# e-Tapperhandpiece11.net
KiCad netlist of a schematic drawn in EAGLE
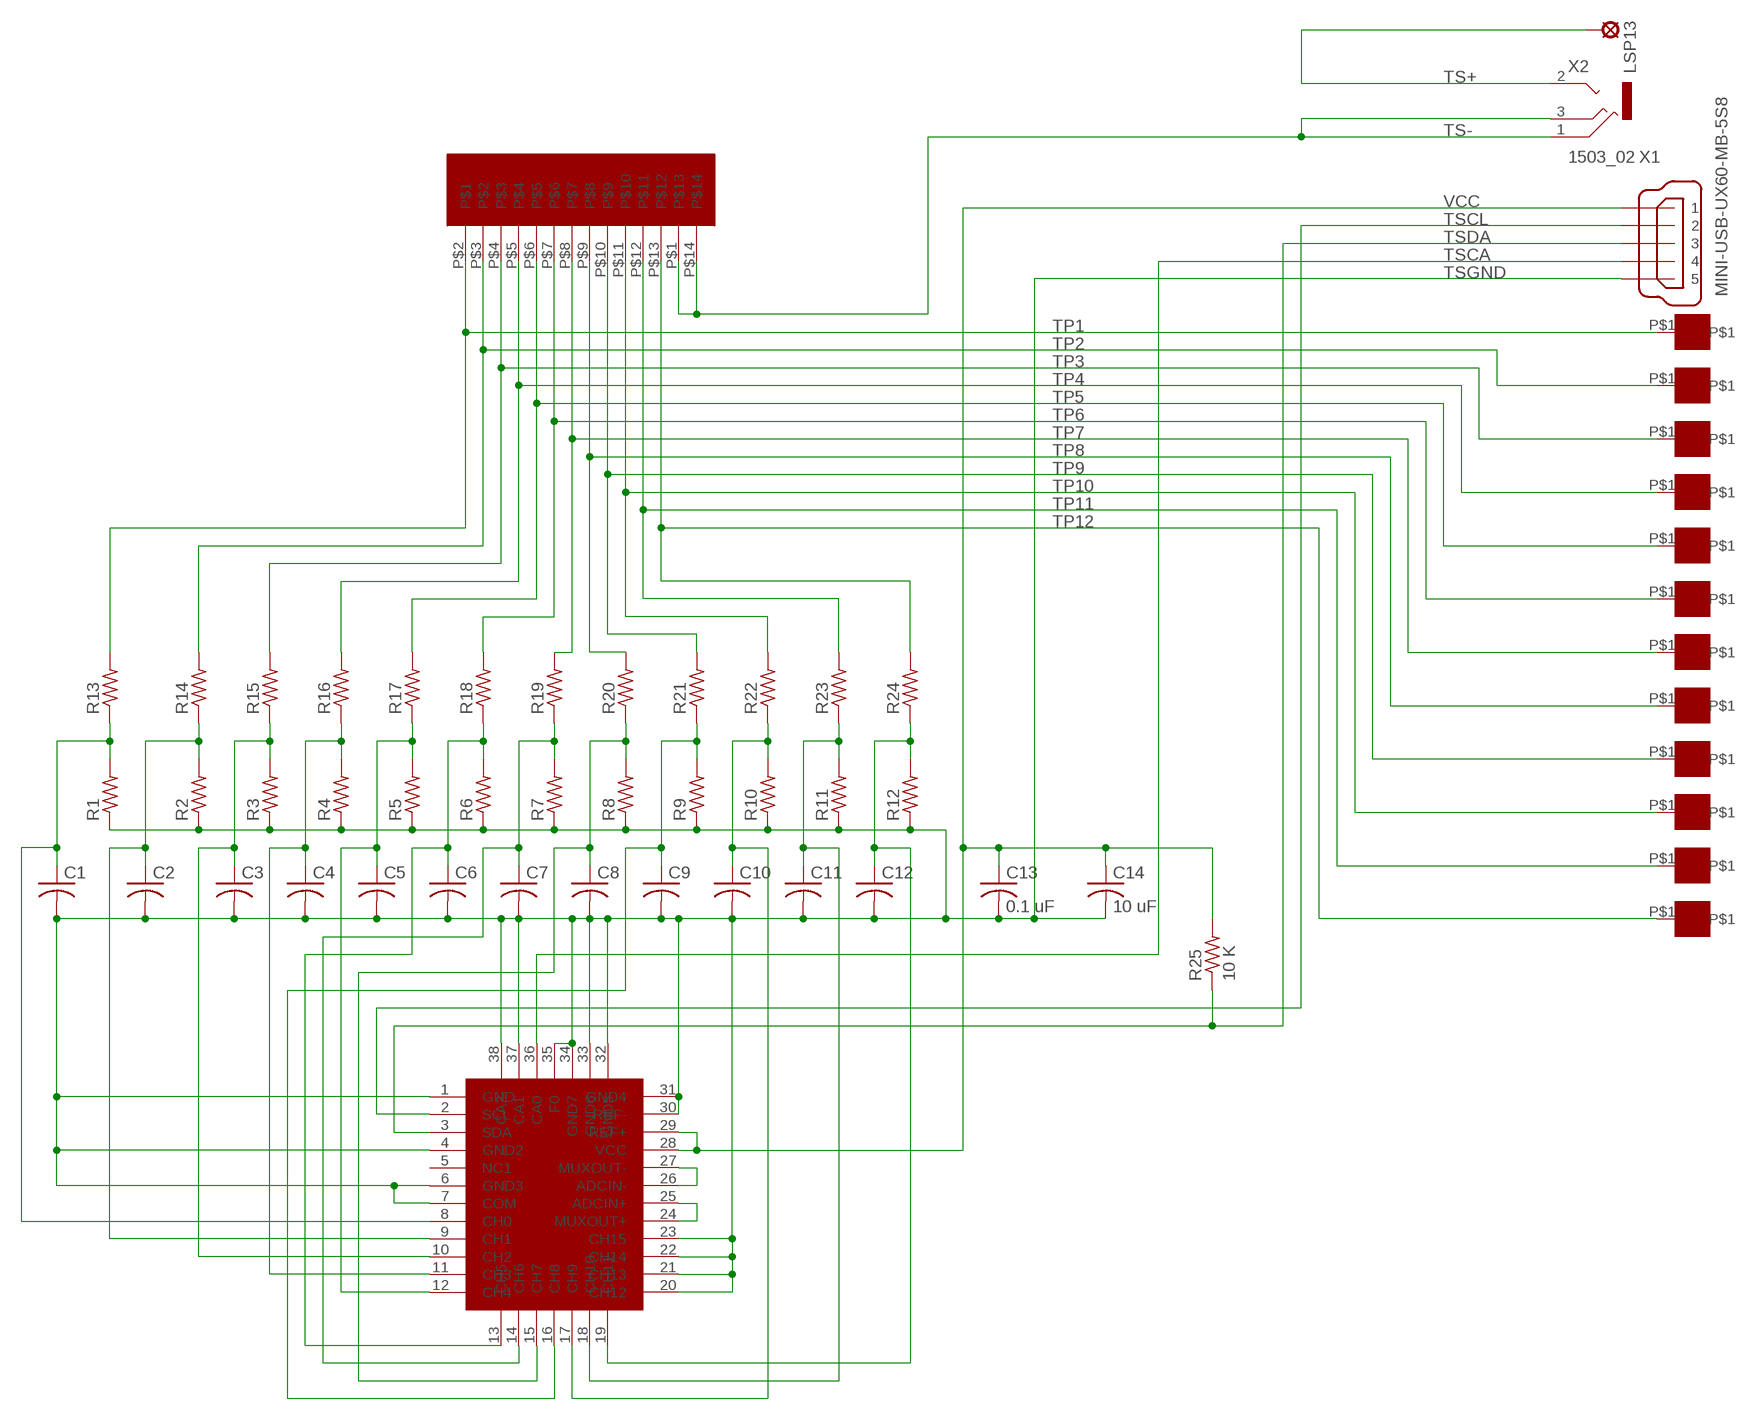
[diagram p0: schematic, sheet 1]

(export (version "E")
  (design (tool "Eeschema 10.0.6"))
  (components
    (comp (ref "C1")
      (value "C-USC0603")
      (footprint "eagle-import:C0603")
      (libsource (lib "eagle-import") (part "C-USC0603"))
    )
    (comp (ref "C2")
      (value "C-USC0603")
      (footprint "eagle-import:C0603")
      (libsource (lib "eagle-import") (part "C-USC0603"))
    )
    (comp (ref "C3")
      (value "C-USC0603")
      (footprint "eagle-import:C0603")
      (libsource (lib "eagle-import") (part "C-USC0603"))
    )
    (comp (ref "C4")
      (value "C-USC0603")
      (footprint "eagle-import:C0603")
      (libsource (lib "eagle-import") (part "C-USC0603"))
    )
    (comp (ref "C5")
      (value "C-USC0603")
      (footprint "eagle-import:C0603")
      (libsource (lib "eagle-import") (part "C-USC0603"))
    )
    (comp (ref "C6")
      (value "C-USC0603")
      (footprint "eagle-import:C0603")
      (libsource (lib "eagle-import") (part "C-USC0603"))
    )
    (comp (ref "C7")
      (value "C-USC0603")
      (footprint "eagle-import:C0603")
      (libsource (lib "eagle-import") (part "C-USC0603"))
    )
    (comp (ref "C8")
      (value "C-USC0603")
      (footprint "eagle-import:C0603")
      (libsource (lib "eagle-import") (part "C-USC0603"))
    )
    (comp (ref "C9")
      (value "C-USC0603")
      (footprint "eagle-import:C0603")
      (libsource (lib "eagle-import") (part "C-USC0603"))
    )
    (comp (ref "C10")
      (value "C-USC0603")
      (footprint "eagle-import:C0603")
      (libsource (lib "eagle-import") (part "C-USC0603"))
    )
    (comp (ref "C11")
      (value "C-USC0603")
      (footprint "eagle-import:C0603")
      (libsource (lib "eagle-import") (part "C-USC0603"))
    )
    (comp (ref "C12")
      (value "C-USC0603")
      (footprint "eagle-import:C0603")
      (libsource (lib "eagle-import") (part "C-USC0603"))
    )
    (comp (ref "C13")
      (value "0.1 uF")
      (footprint "eagle-import:C0603")
      (libsource (lib "eagle-import") (part "C-USC0603"))
    )
    (comp (ref "C14")
      (value "10 uF")
      (footprint "eagle-import:C0805")
      (libsource (lib "eagle-import") (part "C-USC0805"))
    )
    (comp (ref "LSP13")
      (value "SE11")
      (footprint "eagle-import:SE11")
      (libsource (lib "eagle-import") (part "SE11"))
    )
    (comp (ref "R1")
      (value "R-US_R0402")
      (footprint "eagle-import:R0402")
      (libsource (lib "eagle-import") (part "R-US_R0402"))
    )
    (comp (ref "R2")
      (value "R-US_R0402")
      (footprint "eagle-import:R0402")
      (libsource (lib "eagle-import") (part "R-US_R0402"))
    )
    (comp (ref "R3")
      (value "R-US_R0402")
      (footprint "eagle-import:R0402")
      (libsource (lib "eagle-import") (part "R-US_R0402"))
    )
    (comp (ref "R4")
      (value "R-US_R0402")
      (footprint "eagle-import:R0402")
      (libsource (lib "eagle-import") (part "R-US_R0402"))
    )
    (comp (ref "R5")
      (value "R-US_R0402")
      (footprint "eagle-import:R0402")
      (libsource (lib "eagle-import") (part "R-US_R0402"))
    )
    (comp (ref "R6")
      (value "R-US_R0402")
      (footprint "eagle-import:R0402")
      (libsource (lib "eagle-import") (part "R-US_R0402"))
    )
    (comp (ref "R7")
      (value "R-US_R0402")
      (footprint "eagle-import:R0402")
      (libsource (lib "eagle-import") (part "R-US_R0402"))
    )
    (comp (ref "R8")
      (value "R-US_R0402")
      (footprint "eagle-import:R0402")
      (libsource (lib "eagle-import") (part "R-US_R0402"))
    )
    (comp (ref "R9")
      (value "R-US_R0402")
      (footprint "eagle-import:R0402")
      (libsource (lib "eagle-import") (part "R-US_R0402"))
    )
    (comp (ref "R10")
      (value "R-US_R0402")
      (footprint "eagle-import:R0402")
      (libsource (lib "eagle-import") (part "R-US_R0402"))
    )
    (comp (ref "R11")
      (value "R-US_R0402")
      (footprint "eagle-import:R0402")
      (libsource (lib "eagle-import") (part "R-US_R0402"))
    )
    (comp (ref "R12")
      (value "R-US_R0402")
      (footprint "eagle-import:R0402")
      (libsource (lib "eagle-import") (part "R-US_R0402"))
    )
    (comp (ref "R13")
      (value "R-US_R0402")
      (footprint "eagle-import:R0402")
      (libsource (lib "eagle-import") (part "R-US_R0402"))
    )
    (comp (ref "R14")
      (value "R-US_R0402")
      (footprint "eagle-import:R0402")
      (libsource (lib "eagle-import") (part "R-US_R0402"))
    )
    (comp (ref "R15")
      (value "R-US_R0402")
      (footprint "eagle-import:R0402")
      (libsource (lib "eagle-import") (part "R-US_R0402"))
    )
    (comp (ref "R16")
      (value "R-US_R0402")
      (footprint "eagle-import:R0402")
      (libsource (lib "eagle-import") (part "R-US_R0402"))
    )
    (comp (ref "R17")
      (value "R-US_R0402")
      (footprint "eagle-import:R0402")
      (libsource (lib "eagle-import") (part "R-US_R0402"))
    )
    (comp (ref "R18")
      (value "R-US_R0402")
      (footprint "eagle-import:R0402")
      (libsource (lib "eagle-import") (part "R-US_R0402"))
    )
    (comp (ref "R19")
      (value "R-US_R0402")
      (footprint "eagle-import:R0402")
      (libsource (lib "eagle-import") (part "R-US_R0402"))
    )
    (comp (ref "R20")
      (value "R-US_R0402")
      (footprint "eagle-import:R0402")
      (libsource (lib "eagle-import") (part "R-US_R0402"))
    )
    (comp (ref "R21")
      (value "R-US_R0402")
      (footprint "eagle-import:R0402")
      (libsource (lib "eagle-import") (part "R-US_R0402"))
    )
    (comp (ref "R22")
      (value "R-US_R0402")
      (footprint "eagle-import:R0402")
      (libsource (lib "eagle-import") (part "R-US_R0402"))
    )
    (comp (ref "R23")
      (value "R-US_R0402")
      (footprint "eagle-import:R0402")
      (libsource (lib "eagle-import") (part "R-US_R0402"))
    )
    (comp (ref "R24")
      (value "R-US_R0402")
      (footprint "eagle-import:R0402")
      (libsource (lib "eagle-import") (part "R-US_R0402"))
    )
    (comp (ref "R25")
      (value "10 K")
      (footprint "eagle-import:R0402")
      (libsource (lib "eagle-import") (part "R-US_R0402"))
    )
    (comp (ref "TSP1")
      (value "ET1")
      (footprint "eagle-import:ET1")
      (libsource (lib "eagle-import") (part "ET1"))
    )
    (comp (ref "TSP2")
      (value "ET1")
      (footprint "eagle-import:ET1")
      (libsource (lib "eagle-import") (part "ET1"))
    )
    (comp (ref "TSP3")
      (value "ET1")
      (footprint "eagle-import:ET1")
      (libsource (lib "eagle-import") (part "ET1"))
    )
    (comp (ref "TSP4")
      (value "ET1")
      (footprint "eagle-import:ET1")
      (libsource (lib "eagle-import") (part "ET1"))
    )
    (comp (ref "TSP5")
      (value "ET1")
      (footprint "eagle-import:ET1")
      (libsource (lib "eagle-import") (part "ET1"))
    )
    (comp (ref "TSP6")
      (value "ET1")
      (footprint "eagle-import:ET1")
      (libsource (lib "eagle-import") (part "ET1"))
    )
    (comp (ref "TSP7")
      (value "ET1")
      (footprint "eagle-import:ET1")
      (libsource (lib "eagle-import") (part "ET1"))
    )
    (comp (ref "TSP8")
      (value "ET1")
      (footprint "eagle-import:ET1")
      (libsource (lib "eagle-import") (part "ET1"))
    )
    (comp (ref "TSP9")
      (value "ET1")
      (footprint "eagle-import:ET1")
      (libsource (lib "eagle-import") (part "ET1"))
    )
    (comp (ref "TSP10")
      (value "ET1")
      (footprint "eagle-import:ET1")
      (libsource (lib "eagle-import") (part "ET1"))
    )
    (comp (ref "TSP11")
      (value "ET1")
      (footprint "eagle-import:ET1")
      (libsource (lib "eagle-import") (part "ET1"))
    )
    (comp (ref "TSP12")
      (value "ET1")
      (footprint "eagle-import:ET1")
      (libsource (lib "eagle-import") (part "ET1"))
    )
    (comp (ref "U$1")
      (value "LTC2497")
      (footprint "eagle-import:QFN38-5X7")
      (libsource (lib "eagle-import") (part "LTC2497"))
    )
    (comp (ref "U$2")
      (value "SS112D01")
      (footprint "eagle-import:SS112D01")
      (libsource (lib "eagle-import") (part "SS112D01"))
    )
    (comp (ref "X1")
      (value "MINI-USB-UX60-MB-5S8")
      (footprint "eagle-import:UX60-MB-5S8")
      (libsource (lib "eagle-import") (part "MINI-USB-UX60-MB-5S8"))
    )
    (comp (ref "X2")
      (value "1503_02")
      (footprint "eagle-import:1503_02")
      (libsource (lib "eagle-import") (part "1503_02"))
    )
  )
  (nets
    (net (code "1") (name "/TP1") (class "Default")
      (node (ref "R13") (pin "2") (pinfunction "2_2") (pintype "passive"))
      (node (ref "TSP1") (pin "P$1") (pinfunction "P$1_P$1") (pintype "bidirectional"))
      (node (ref "U$2") (pin "P$2") (pinfunction "P$1_P$2") (pintype "bidirectional"))
    )
    (net (code "2") (name "/TP2") (class "Default")
      (node (ref "R14") (pin "2") (pinfunction "2_2") (pintype "passive"))
      (node (ref "TSP2") (pin "P$1") (pinfunction "P$1_P$1") (pintype "bidirectional"))
      (node (ref "U$2") (pin "P$3") (pinfunction "P$2_P$3") (pintype "bidirectional"))
    )
    (net (code "3") (name "/TP3") (class "Default")
      (node (ref "R15") (pin "2") (pinfunction "2_2") (pintype "passive"))
      (node (ref "TSP3") (pin "P$1") (pinfunction "P$1_P$1") (pintype "bidirectional"))
      (node (ref "U$2") (pin "P$4") (pinfunction "P$3_P$4") (pintype "bidirectional"))
    )
    (net (code "4") (name "/TP4") (class "Default")
      (node (ref "R16") (pin "2") (pinfunction "2_2") (pintype "passive"))
      (node (ref "TSP4") (pin "P$1") (pinfunction "P$1_P$1") (pintype "bidirectional"))
      (node (ref "U$2") (pin "P$5") (pinfunction "P$4_P$5") (pintype "bidirectional"))
    )
    (net (code "5") (name "/TP5") (class "Default")
      (node (ref "R17") (pin "2") (pinfunction "2_2") (pintype "passive"))
      (node (ref "TSP5") (pin "P$1") (pinfunction "P$1_P$1") (pintype "bidirectional"))
      (node (ref "U$2") (pin "P$6") (pinfunction "P$5_P$6") (pintype "bidirectional"))
    )
    (net (code "6") (name "/TP6") (class "Default")
      (node (ref "R18") (pin "2") (pinfunction "2_2") (pintype "passive"))
      (node (ref "TSP6") (pin "P$1") (pinfunction "P$1_P$1") (pintype "bidirectional"))
      (node (ref "U$2") (pin "P$7") (pinfunction "P$6_P$7") (pintype "bidirectional"))
    )
    (net (code "7") (name "/TP7") (class "Default")
      (node (ref "R19") (pin "2") (pinfunction "2_2") (pintype "passive"))
      (node (ref "TSP7") (pin "P$1") (pinfunction "P$1_P$1") (pintype "bidirectional"))
      (node (ref "U$2") (pin "P$8") (pinfunction "P$7_P$8") (pintype "bidirectional"))
    )
    (net (code "8") (name "/TP8") (class "Default")
      (node (ref "R20") (pin "2") (pinfunction "2_2") (pintype "passive"))
      (node (ref "TSP8") (pin "P$1") (pinfunction "P$1_P$1") (pintype "bidirectional"))
      (node (ref "U$2") (pin "P$9") (pinfunction "P$8_P$9") (pintype "bidirectional"))
    )
    (net (code "9") (name "/TP9") (class "Default")
      (node (ref "R21") (pin "2") (pinfunction "2_2") (pintype "passive"))
      (node (ref "TSP9") (pin "P$1") (pinfunction "P$1_P$1") (pintype "bidirectional"))
      (node (ref "U$2") (pin "P$10") (pinfunction "P$9_P$10") (pintype "bidirectional"))
    )
    (net (code "10") (name "/TP10") (class "Default")
      (node (ref "R22") (pin "2") (pinfunction "2_2") (pintype "passive"))
      (node (ref "TSP10") (pin "P$1") (pinfunction "P$1_P$1") (pintype "bidirectional"))
      (node (ref "U$2") (pin "P$11") (pinfunction "P$10_P$11") (pintype "bidirectional"))
    )
    (net (code "11") (name "/TP11") (class "Default")
      (node (ref "R23") (pin "2") (pinfunction "2_2") (pintype "passive"))
      (node (ref "TSP11") (pin "P$1") (pinfunction "P$1_P$1") (pintype "bidirectional"))
      (node (ref "U$2") (pin "P$12") (pinfunction "P$11_P$12") (pintype "bidirectional"))
    )
    (net (code "12") (name "/TP12") (class "Default")
      (node (ref "R24") (pin "2") (pinfunction "2_2") (pintype "passive"))
      (node (ref "TSP12") (pin "P$1") (pinfunction "P$1_P$1") (pintype "bidirectional"))
      (node (ref "U$2") (pin "P$13") (pinfunction "P$12_P$13") (pintype "bidirectional"))
    )
    (net (code "13") (name "/TS+") (class "Default")
      (node (ref "LSP13") (pin "MP") (pinfunction "MP_MP") (pintype "passive"))
      (node (ref "X2") (pin "2") (pinfunction "2_2") (pintype "passive"))
    )
    (net (code "14") (name "/TS-") (class "Default")
      (node (ref "U$2") (pin "P$1") (pinfunction "P$13_P$1") (pintype "bidirectional"))
      (node (ref "U$2") (pin "P$14") (pinfunction "P$14_P$14") (pintype "bidirectional"))
      (node (ref "X2") (pin "1") (pinfunction "1_1") (pintype "passive"))
      (node (ref "X2") (pin "3") (pinfunction "3_3") (pintype "passive"))
    )
    (net (code "15") (name "/TSCA") (class "Default")
      (node (ref "U$1") (pin "36") (pinfunction "CA0_36") (pintype "bidirectional"))
      (node (ref "X1") (pin "4") (pinfunction "4_4") (pintype "input"))
    )
    (net (code "16") (name "/TSCL") (class "Default")
      (node (ref "U$1") (pin "2") (pinfunction "SCL_2") (pintype "bidirectional"))
      (node (ref "X1") (pin "2") (pinfunction "2_2") (pintype "input"))
    )
    (net (code "17") (name "/TSDA") (class "Default")
      (node (ref "R25") (pin "1") (pinfunction "1_1") (pintype "passive"))
      (node (ref "U$1") (pin "3") (pinfunction "SDA_3") (pintype "bidirectional"))
      (node (ref "X1") (pin "3") (pinfunction "3_3") (pintype "input"))
    )
    (net (code "18") (name "/TSGND") (class "Default")
      (node (ref "C1") (pin "2") (pinfunction "2_2") (pintype "passive"))
      (node (ref "C10") (pin "2") (pinfunction "2_2") (pintype "passive"))
      (node (ref "C11") (pin "2") (pinfunction "2_2") (pintype "passive"))
      (node (ref "C12") (pin "2") (pinfunction "2_2") (pintype "passive"))
      (node (ref "C13") (pin "2") (pinfunction "2_2") (pintype "passive"))
      (node (ref "C14") (pin "2") (pinfunction "2_2") (pintype "passive"))
      (node (ref "C2") (pin "2") (pinfunction "2_2") (pintype "passive"))
      (node (ref "C3") (pin "2") (pinfunction "2_2") (pintype "passive"))
      (node (ref "C4") (pin "2") (pinfunction "2_2") (pintype "passive"))
      (node (ref "C5") (pin "2") (pinfunction "2_2") (pintype "passive"))
      (node (ref "C6") (pin "2") (pinfunction "2_2") (pintype "passive"))
      (node (ref "C7") (pin "2") (pinfunction "2_2") (pintype "passive"))
      (node (ref "C8") (pin "2") (pinfunction "2_2") (pintype "passive"))
      (node (ref "C9") (pin "2") (pinfunction "2_2") (pintype "passive"))
      (node (ref "R1") (pin "1") (pinfunction "1_1") (pintype "passive"))
      (node (ref "R10") (pin "1") (pinfunction "1_1") (pintype "passive"))
      (node (ref "R11") (pin "1") (pinfunction "1_1") (pintype "passive"))
      (node (ref "R12") (pin "1") (pinfunction "1_1") (pintype "passive"))
      (node (ref "R2") (pin "1") (pinfunction "1_1") (pintype "passive"))
      (node (ref "R3") (pin "1") (pinfunction "1_1") (pintype "passive"))
      (node (ref "R4") (pin "1") (pinfunction "1_1") (pintype "passive"))
      (node (ref "R5") (pin "1") (pinfunction "1_1") (pintype "passive"))
      (node (ref "R6") (pin "1") (pinfunction "1_1") (pintype "passive"))
      (node (ref "R7") (pin "1") (pinfunction "1_1") (pintype "passive"))
      (node (ref "R8") (pin "1") (pinfunction "1_1") (pintype "passive"))
      (node (ref "R9") (pin "1") (pinfunction "1_1") (pintype "passive"))
      (node (ref "U$1") (pin "1") (pinfunction "GND_1") (pintype "power_in"))
      (node (ref "U$1") (pin "20") (pinfunction "CH12_20") (pintype "input"))
      (node (ref "U$1") (pin "21") (pinfunction "CH13_21") (pintype "input"))
      (node (ref "U$1") (pin "22") (pinfunction "CH14_22") (pintype "input"))
      (node (ref "U$1") (pin "23") (pinfunction "CH15_23") (pintype "input"))
      (node (ref "U$1") (pin "30") (pinfunction "REF-_30") (pintype "bidirectional"))
      (node (ref "U$1") (pin "31") (pinfunction "GND4_31") (pintype "power_in"))
      (node (ref "U$1") (pin "32") (pinfunction "GND5_32") (pintype "power_in"))
      (node (ref "U$1") (pin "33") (pinfunction "GND6_33") (pintype "power_in"))
      (node (ref "U$1") (pin "34") (pinfunction "GND7_34") (pintype "power_in"))
      (node (ref "U$1") (pin "35") (pinfunction "F0_35") (pintype "bidirectional"))
      (node (ref "U$1") (pin "37") (pinfunction "CA1_37") (pintype "bidirectional"))
      (node (ref "U$1") (pin "38") (pinfunction "CA2_38") (pintype "bidirectional"))
      (node (ref "U$1") (pin "4") (pinfunction "GND2_4") (pintype "power_in"))
      (node (ref "U$1") (pin "6") (pinfunction "GND3_6") (pintype "power_in"))
      (node (ref "U$1") (pin "7") (pinfunction "COM_7") (pintype "power_in"))
      (node (ref "X1") (pin "5") (pinfunction "5_5") (pintype "input"))
    )
    (net (code "19") (name "/VCC") (class "Default")
      (node (ref "C13") (pin "1") (pinfunction "1_1") (pintype "passive"))
      (node (ref "C14") (pin "1") (pinfunction "1_1") (pintype "passive"))
      (node (ref "R25") (pin "2") (pinfunction "2_2") (pintype "passive"))
      (node (ref "U$1") (pin "28") (pinfunction "VCC_28") (pintype "power_in"))
      (node (ref "U$1") (pin "29") (pinfunction "REF+_29") (pintype "bidirectional"))
      (node (ref "X1") (pin "1") (pinfunction "1_1") (pintype "input"))
    )
    (net (code "20") (name "Net-(U$1-ADCIN+)") (class "Default")
      (node (ref "U$1") (pin "24") (pinfunction "MUXOUT+_24") (pintype "bidirectional"))
      (node (ref "U$1") (pin "25") (pinfunction "ADCIN+_25") (pintype "bidirectional"))
    )
    (net (code "21") (name "Net-(U$1-ADCIN-)") (class "Default")
      (node (ref "U$1") (pin "26") (pinfunction "ADCIN-_26") (pintype "bidirectional"))
      (node (ref "U$1") (pin "27") (pinfunction "MUXOUT-_27") (pintype "bidirectional"))
    )
    (net (code "22") (name "Net-(U$1-CH0)") (class "Default")
      (node (ref "C1") (pin "1") (pinfunction "1_1") (pintype "passive"))
      (node (ref "R1") (pin "2") (pinfunction "2_2") (pintype "passive"))
      (node (ref "R13") (pin "1") (pinfunction "1_1") (pintype "passive"))
      (node (ref "U$1") (pin "8") (pinfunction "CH0_8") (pintype "input"))
    )
    (net (code "23") (name "Net-(U$1-CH1)") (class "Default")
      (node (ref "C2") (pin "1") (pinfunction "1_1") (pintype "passive"))
      (node (ref "R14") (pin "1") (pinfunction "1_1") (pintype "passive"))
      (node (ref "R2") (pin "2") (pinfunction "2_2") (pintype "passive"))
      (node (ref "U$1") (pin "9") (pinfunction "CH1_9") (pintype "input"))
    )
    (net (code "24") (name "Net-(U$1-CH2)") (class "Default")
      (node (ref "C3") (pin "1") (pinfunction "1_1") (pintype "passive"))
      (node (ref "R15") (pin "1") (pinfunction "1_1") (pintype "passive"))
      (node (ref "R3") (pin "2") (pinfunction "2_2") (pintype "passive"))
      (node (ref "U$1") (pin "10") (pinfunction "CH2_10") (pintype "input"))
    )
    (net (code "25") (name "Net-(U$1-CH3)") (class "Default")
      (node (ref "C4") (pin "1") (pinfunction "1_1") (pintype "passive"))
      (node (ref "R16") (pin "1") (pinfunction "1_1") (pintype "passive"))
      (node (ref "R4") (pin "2") (pinfunction "2_2") (pintype "passive"))
      (node (ref "U$1") (pin "11") (pinfunction "CH3_11") (pintype "input"))
    )
    (net (code "26") (name "Net-(U$1-CH4)") (class "Default")
      (node (ref "C5") (pin "1") (pinfunction "1_1") (pintype "passive"))
      (node (ref "R17") (pin "1") (pinfunction "1_1") (pintype "passive"))
      (node (ref "R5") (pin "2") (pinfunction "2_2") (pintype "passive"))
      (node (ref "U$1") (pin "12") (pinfunction "CH4_12") (pintype "input"))
    )
    (net (code "27") (name "Net-(U$1-CH5)") (class "Default")
      (node (ref "C6") (pin "1") (pinfunction "1_1") (pintype "passive"))
      (node (ref "R18") (pin "1") (pinfunction "1_1") (pintype "passive"))
      (node (ref "R6") (pin "2") (pinfunction "2_2") (pintype "passive"))
      (node (ref "U$1") (pin "13") (pinfunction "CH5_13") (pintype "input"))
    )
    (net (code "28") (name "Net-(U$1-CH6)") (class "Default")
      (node (ref "C7") (pin "1") (pinfunction "1_1") (pintype "passive"))
      (node (ref "R19") (pin "1") (pinfunction "1_1") (pintype "passive"))
      (node (ref "R7") (pin "2") (pinfunction "2_2") (pintype "passive"))
      (node (ref "U$1") (pin "14") (pinfunction "CH6_14") (pintype "input"))
    )
    (net (code "29") (name "Net-(U$1-CH7)") (class "Default")
      (node (ref "C8") (pin "1") (pinfunction "1_1") (pintype "passive"))
      (node (ref "R20") (pin "1") (pinfunction "1_1") (pintype "passive"))
      (node (ref "R8") (pin "2") (pinfunction "2_2") (pintype "passive"))
      (node (ref "U$1") (pin "15") (pinfunction "CH7_15") (pintype "input"))
    )
    (net (code "30") (name "Net-(U$1-CH8)") (class "Default")
      (node (ref "C9") (pin "1") (pinfunction "1_1") (pintype "passive"))
      (node (ref "R21") (pin "1") (pinfunction "1_1") (pintype "passive"))
      (node (ref "R9") (pin "2") (pinfunction "2_2") (pintype "passive"))
      (node (ref "U$1") (pin "16") (pinfunction "CH8_16") (pintype "input"))
    )
    (net (code "31") (name "Net-(U$1-CH9)") (class "Default")
      (node (ref "C10") (pin "1") (pinfunction "1_1") (pintype "passive"))
      (node (ref "R10") (pin "2") (pinfunction "2_2") (pintype "passive"))
      (node (ref "R22") (pin "1") (pinfunction "1_1") (pintype "passive"))
      (node (ref "U$1") (pin "17") (pinfunction "CH9_17") (pintype "input"))
    )
    (net (code "32") (name "Net-(U$1-CH10)") (class "Default")
      (node (ref "C11") (pin "1") (pinfunction "1_1") (pintype "passive"))
      (node (ref "R11") (pin "2") (pinfunction "2_2") (pintype "passive"))
      (node (ref "R23") (pin "1") (pinfunction "1_1") (pintype "passive"))
      (node (ref "U$1") (pin "18") (pinfunction "CH10_18") (pintype "input"))
    )
    (net (code "33") (name "Net-(U$1-CH11)") (class "Default")
      (node (ref "C12") (pin "1") (pinfunction "1_1") (pintype "passive"))
      (node (ref "R12") (pin "2") (pinfunction "2_2") (pintype "passive"))
      (node (ref "R24") (pin "1") (pinfunction "1_1") (pintype "passive"))
      (node (ref "U$1") (pin "19") (pinfunction "CH11_19") (pintype "input"))
    )
    (net (code "34") (name "unconnected-(U$1-NC1-Pad5)") (class "Default")
      (node (ref "U$1") (pin "5") (pinfunction "NC1_5") (pintype "no_connect"))
    )
    (net (code "35") (name "unconnected-(X2-2-Pad2@2)") (class "Default")
      (node (ref "X2") (pin "2@2") (pinfunction "2_2@2") (pintype "passive"))
    )
  )
)
